# isoJTAG-Isolation.net
KiCad netlist of a schematic drawn in Altium Designer
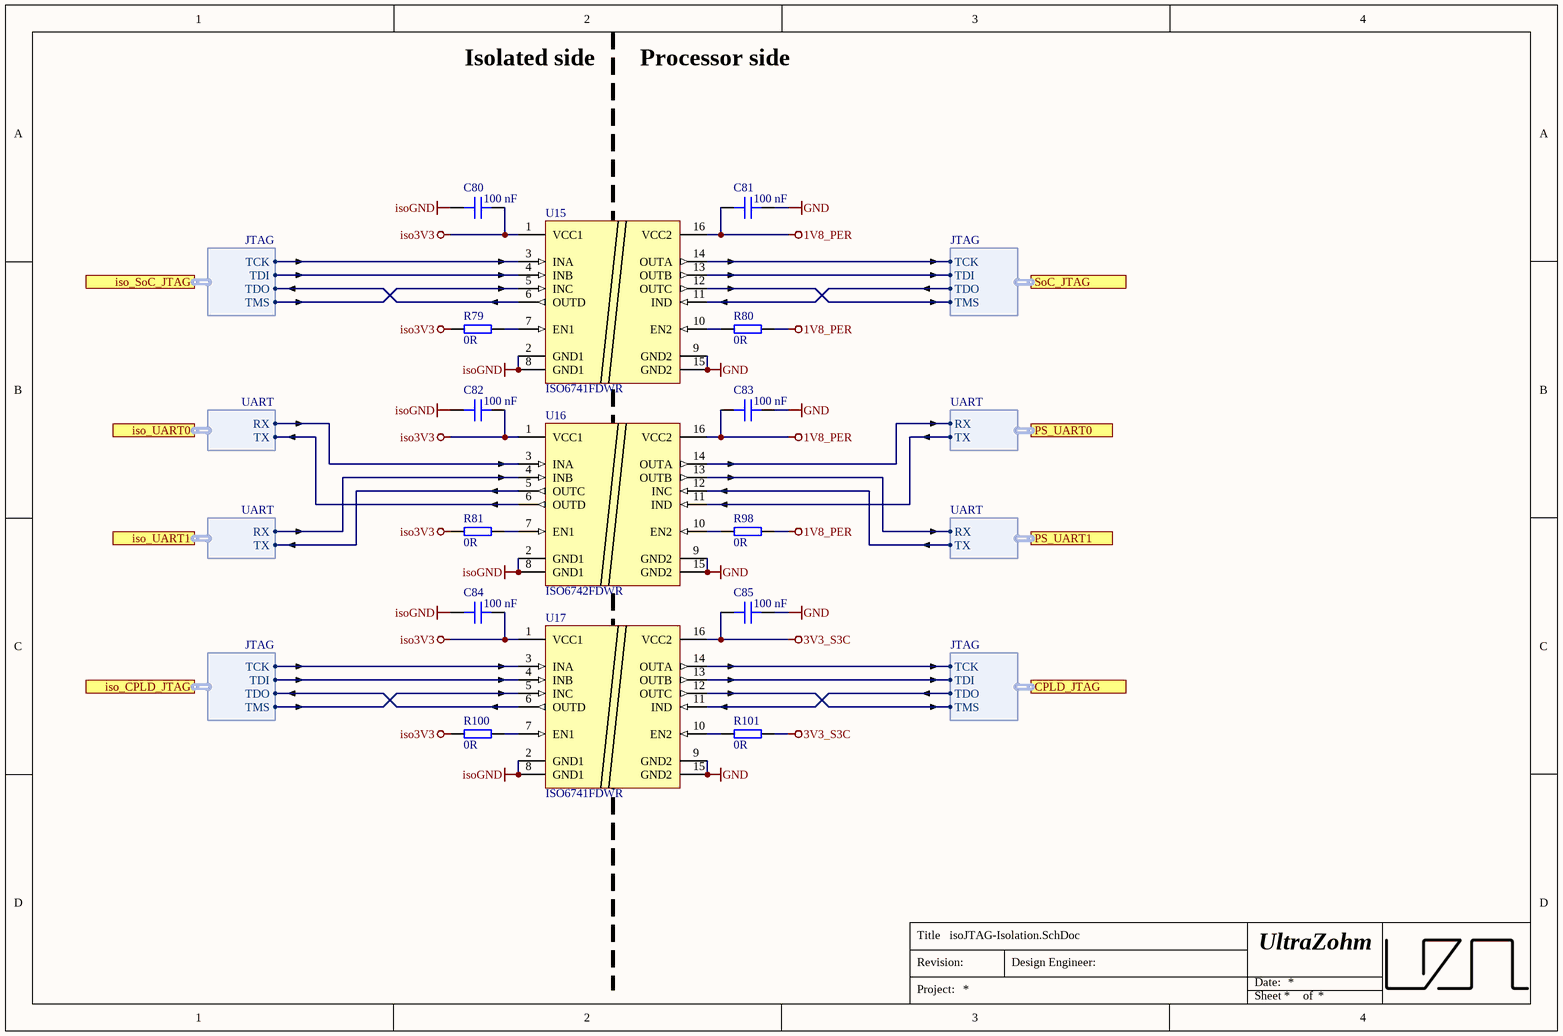
[diagram p0: isoJTAG-Isolation.SchDoc]

(export (version "E")
  (design (tool "Eeschema 10.0.6"))
  (components
    (comp (ref "C80")
      (value "100 nF")
      (footprint "C_0402_TE")
      (description "50V 100nF X7R ±10% 0402 Multilayer Ceramic Capacitors MLCC - SMD/SMT ROHS")
      (fields
        (field (name "MANUFACTURER PART NUMBER") "GRM155R71H104KE14D")
        (field (name "MANUFACTURER") "Murata Electronics")
        (field (name "CREATED FROM") "AGeiger")
      )
      (libsource (lib "user") (part "Capacitor"))
    )
    (comp (ref "C81")
      (value "100 nF")
      (footprint "C_0402_TE")
      (description "50V 100nF X7R ±10% 0402 Multilayer Ceramic Capacitors MLCC - SMD/SMT ROHS")
      (fields
        (field (name "MANUFACTURER PART NUMBER") "GRM155R71H104KE14D")
        (field (name "MANUFACTURER") "Murata Electronics")
        (field (name "CREATED FROM") "AGeiger")
      )
      (libsource (lib "user") (part "Capacitor"))
    )
    (comp (ref "C82")
      (value "100 nF")
      (footprint "C_0402_TE")
      (description "50V 100nF X7R ±10% 0402 Multilayer Ceramic Capacitors MLCC - SMD/SMT ROHS")
      (fields
        (field (name "MANUFACTURER PART NUMBER") "GRM155R71H104KE14D")
        (field (name "MANUFACTURER") "Murata Electronics")
        (field (name "CREATED FROM") "AGeiger")
      )
      (libsource (lib "user") (part "Capacitor"))
    )
    (comp (ref "C83")
      (value "100 nF")
      (footprint "C_0402_TE")
      (description "50V 100nF X7R ±10% 0402 Multilayer Ceramic Capacitors MLCC - SMD/SMT ROHS")
      (fields
        (field (name "MANUFACTURER PART NUMBER") "GRM155R71H104KE14D")
        (field (name "MANUFACTURER") "Murata Electronics")
        (field (name "CREATED FROM") "AGeiger")
      )
      (libsource (lib "user") (part "Capacitor"))
    )
    (comp (ref "C84")
      (value "100 nF")
      (footprint "C_0402_TE")
      (description "50V 100nF X7R ±10% 0402 Multilayer Ceramic Capacitors MLCC - SMD/SMT ROHS")
      (fields
        (field (name "MANUFACTURER PART NUMBER") "GRM155R71H104KE14D")
        (field (name "MANUFACTURER") "Murata Electronics")
        (field (name "CREATED FROM") "AGeiger")
      )
      (libsource (lib "user") (part "Capacitor"))
    )
    (comp (ref "C85")
      (value "100 nF")
      (footprint "C_0402_TE")
      (description "50V 100nF X7R ±10% 0402 Multilayer Ceramic Capacitors MLCC - SMD/SMT ROHS")
      (fields
        (field (name "MANUFACTURER PART NUMBER") "GRM155R71H104KE14D")
        (field (name "MANUFACTURER") "Murata Electronics")
        (field (name "CREATED FROM") "AGeiger")
      )
      (libsource (lib "user") (part "Capacitor"))
    )
    (comp (ref "R79")
      (value "0R")
      (footprint "R_0402_TE")
      (description "62.5mW Thick Film Resistors 50V 0Ω 0402 Chip Resistor - Surface Mount ROHS")
      (fields
        (field (name "MANUFACTURER PART NUMBER") "RC0402JR-070RL")
        (field (name "MANUFACTURER") "YAGEO")
        (field (name "CREATED FROM") "AGeiger")
      )
      (libsource (lib "user") (part "Resistor"))
    )
    (comp (ref "R80")
      (value "0R")
      (footprint "R_0402_TE")
      (description "62.5mW Thick Film Resistors 50V 0Ω 0402 Chip Resistor - Surface Mount ROHS")
      (fields
        (field (name "MANUFACTURER PART NUMBER") "RC0402JR-070RL")
        (field (name "MANUFACTURER") "YAGEO")
        (field (name "CREATED FROM") "AGeiger")
      )
      (libsource (lib "user") (part "Resistor"))
    )
    (comp (ref "R81")
      (value "0R")
      (footprint "R_0402_TE")
      (description "62.5mW Thick Film Resistors 50V 0Ω 0402 Chip Resistor - Surface Mount ROHS")
      (fields
        (field (name "MANUFACTURER PART NUMBER") "RC0402JR-070RL")
        (field (name "MANUFACTURER") "YAGEO")
        (field (name "CREATED FROM") "AGeiger")
      )
      (libsource (lib "user") (part "Resistor"))
    )
    (comp (ref "R98")
      (value "0R")
      (footprint "R_0402_TE")
      (description "62.5mW Thick Film Resistors 50V 0Ω 0402 Chip Resistor - Surface Mount ROHS")
      (fields
        (field (name "MANUFACTURER PART NUMBER") "RC0402JR-070RL")
        (field (name "MANUFACTURER") "YAGEO")
        (field (name "CREATED FROM") "AGeiger")
      )
      (libsource (lib "user") (part "Resistor"))
    )
    (comp (ref "R100")
      (value "0R")
      (footprint "R_0402_TE")
      (description "62.5mW Thick Film Resistors 50V 0Ω 0402 Chip Resistor - Surface Mount ROHS")
      (fields
        (field (name "MANUFACTURER PART NUMBER") "RC0402JR-070RL")
        (field (name "MANUFACTURER") "YAGEO")
        (field (name "CREATED FROM") "AGeiger")
      )
      (libsource (lib "user") (part "Resistor"))
    )
    (comp (ref "R101")
      (value "0R")
      (footprint "R_0402_TE")
      (description "62.5mW Thick Film Resistors 50V 0Ω 0402 Chip Resistor - Surface Mount ROHS")
      (fields
        (field (name "MANUFACTURER PART NUMBER") "RC0402JR-070RL")
        (field (name "MANUFACTURER") "YAGEO")
        (field (name "CREATED FROM") "AGeiger")
      )
      (libsource (lib "user") (part "Resistor"))
    )
    (comp (ref "U15")
      (value "ISO6741FDWR")
      (footprint "SOIC127P1030X265-16N")
      (description "Digital Isolators General-purpose, quad-channel, 3/1 digital isolator 16-SOIC -40 to 125")
      (fields
        (field (name "MANUFACTURER") "Texas Instruments")
        (field (name "LCSC PART NUMBER") "C5216433")
        (field (name "CREATED FROM") "FRosner")
      )
      (libsource (lib "user") (part "ISO6741"))
    )
    (comp (ref "U16")
      (value "ISO6742FDWR")
      (footprint "SOIC127P1030X265-16N")
      (description "Digital Isolators General-purpose, quad-channel, 2/2 digital isolator")
      (fields
        (field (name "MANUFACTURER") "Texas Instruments")
        (field (name "LCSC PART NUMBER") "C5216408")
        (field (name "CREATED FROM") "FRosner")
      )
      (libsource (lib "user") (part "ISO6742"))
    )
    (comp (ref "U17")
      (value "ISO6741FDWR")
      (footprint "SOIC127P1030X265-16N")
      (description "Digital Isolators General-purpose, quad-channel, 3/1 digital isolator 16-SOIC -40 to 125")
      (fields
        (field (name "MANUFACTURER") "Texas Instruments")
        (field (name "LCSC PART NUMBER") "C5216433")
        (field (name "CREATED FROM") "FRosner")
      )
      (libsource (lib "user") (part "ISO6741"))
    )
  )
  (nets
    (net (code "5") (name "1V8_PER") (class "Default")
      (node (ref "C81") (pin "2") (pinfunction "2_2") (pintype "passive"))
      (node (ref "C83") (pin "2") (pinfunction "2_2") (pintype "passive"))
      (node (ref "R80") (pin "2") (pinfunction "2_2") (pintype "passive"))
      (node (ref "R98") (pin "2") (pinfunction "2_2") (pintype "passive"))
      (node (ref "U15") (pin "16") (pinfunction "VCC2_16") (pintype "power_in"))
      (node (ref "U16") (pin "16") (pinfunction "VCC2_16") (pintype "power_in"))
    )
    (net (code "6") (name "3V3_S3C") (class "Default")
      (node (ref "C85") (pin "2") (pinfunction "2_2") (pintype "passive"))
      (node (ref "R101") (pin "2") (pinfunction "2_2") (pintype "passive"))
      (node (ref "U17") (pin "16") (pinfunction "VCC2_16") (pintype "power_in"))
    )
    (net (code "7") (name "GND") (class "Default")
      (node (ref "C81") (pin "1") (pinfunction "1_1") (pintype "passive"))
      (node (ref "C83") (pin "1") (pinfunction "1_1") (pintype "passive"))
      (node (ref "C85") (pin "1") (pinfunction "1_1") (pintype "passive"))
      (node (ref "U15") (pin "15") (pinfunction "GND2_15") (pintype "power_in"))
      (node (ref "U15") (pin "9") (pinfunction "GND2_9") (pintype "power_in"))
      (node (ref "U16") (pin "15") (pinfunction "GND2_15") (pintype "power_in"))
      (node (ref "U16") (pin "9") (pinfunction "GND2_9") (pintype "power_in"))
      (node (ref "U17") (pin "15") (pinfunction "GND2_15") (pintype "power_in"))
      (node (ref "U17") (pin "9") (pinfunction "GND2_9") (pintype "power_in"))
    )
    (net (code "8") (name "Net-(U15-EN1)") (class "Default")
      (node (ref "R79") (pin "2") (pinfunction "2_2") (pintype "passive"))
      (node (ref "U15") (pin "7") (pinfunction "EN1_7") (pintype "input"))
    )
    (net (code "9") (name "Net-(U15-EN2)") (class "Default")
      (node (ref "R80") (pin "1") (pinfunction "1_1") (pintype "passive"))
      (node (ref "U15") (pin "10") (pinfunction "EN2_10") (pintype "input"))
    )
    (net (code "10") (name "Net-(U16-EN1)") (class "Default")
      (node (ref "R81") (pin "2") (pinfunction "2_2") (pintype "passive"))
      (node (ref "U16") (pin "7") (pinfunction "EN1_7") (pintype "input"))
    )
    (net (code "11") (name "Net-(U16-EN2)") (class "Default")
      (node (ref "R98") (pin "1") (pinfunction "1_1") (pintype "passive"))
      (node (ref "U16") (pin "10") (pinfunction "EN2_10") (pintype "input"))
    )
    (net (code "12") (name "Net-(U17-EN1)") (class "Default")
      (node (ref "R100") (pin "2") (pinfunction "2_2") (pintype "passive"))
      (node (ref "U17") (pin "7") (pinfunction "EN1_7") (pintype "input"))
    )
    (net (code "13") (name "Net-(U17-EN2)") (class "Default")
      (node (ref "R101") (pin "1") (pinfunction "1_1") (pintype "passive"))
      (node (ref "U17") (pin "10") (pinfunction "EN2_10") (pintype "input"))
    )
    (net (code "14") (name "iso3V3") (class "Default")
      (node (ref "C80") (pin "1") (pinfunction "1_1") (pintype "passive"))
      (node (ref "C82") (pin "1") (pinfunction "1_1") (pintype "passive"))
      (node (ref "C84") (pin "1") (pinfunction "1_1") (pintype "passive"))
      (node (ref "R100") (pin "1") (pinfunction "1_1") (pintype "passive"))
      (node (ref "R79") (pin "1") (pinfunction "1_1") (pintype "passive"))
      (node (ref "R81") (pin "1") (pinfunction "1_1") (pintype "passive"))
      (node (ref "U15") (pin "1") (pinfunction "VCC1_1") (pintype "power_in"))
      (node (ref "U16") (pin "1") (pinfunction "VCC1_1") (pintype "power_in"))
      (node (ref "U17") (pin "1") (pinfunction "VCC1_1") (pintype "power_in"))
    )
    (net (code "15") (name "isoGND") (class "Default")
      (node (ref "C80") (pin "2") (pinfunction "2_2") (pintype "passive"))
      (node (ref "C82") (pin "2") (pinfunction "2_2") (pintype "passive"))
      (node (ref "C84") (pin "2") (pinfunction "2_2") (pintype "passive"))
      (node (ref "U15") (pin "2") (pinfunction "GND1_2") (pintype "power_in"))
      (node (ref "U15") (pin "8") (pinfunction "GND1_8") (pintype "power_in"))
      (node (ref "U16") (pin "2") (pinfunction "GND1_2") (pintype "power_in"))
      (node (ref "U16") (pin "8") (pinfunction "GND1_8") (pintype "power_in"))
      (node (ref "U17") (pin "2") (pinfunction "GND1_2") (pintype "power_in"))
      (node (ref "U17") (pin "8") (pinfunction "GND1_8") (pintype "power_in"))
    )
    (net (code "16") (name "unconnected-(U15-INA-Pad3)") (class "Default")
      (node (ref "U15") (pin "3") (pinfunction "INA_3") (pintype "input"))
    )
    (net (code "17") (name "unconnected-(U15-INB-Pad4)") (class "Default")
      (node (ref "U15") (pin "4") (pinfunction "INB_4") (pintype "input"))
    )
    (net (code "18") (name "unconnected-(U15-INC-Pad5)") (class "Default")
      (node (ref "U15") (pin "5") (pinfunction "INC_5") (pintype "input"))
    )
    (net (code "19") (name "unconnected-(U15-IND-Pad11)") (class "Default")
      (node (ref "U15") (pin "11") (pinfunction "IND_11") (pintype "input"))
    )
    (net (code "20") (name "unconnected-(U15-OUTA-Pad14)") (class "Default")
      (node (ref "U15") (pin "14") (pinfunction "OUTA_14") (pintype "output"))
    )
    (net (code "21") (name "unconnected-(U15-OUTB-Pad13)") (class "Default")
      (node (ref "U15") (pin "13") (pinfunction "OUTB_13") (pintype "output"))
    )
    (net (code "22") (name "unconnected-(U15-OUTC-Pad12)") (class "Default")
      (node (ref "U15") (pin "12") (pinfunction "OUTC_12") (pintype "output"))
    )
    (net (code "23") (name "unconnected-(U15-OUTD-Pad6)") (class "Default")
      (node (ref "U15") (pin "6") (pinfunction "OUTD_6") (pintype "output"))
    )
    (net (code "24") (name "unconnected-(U16-INA-Pad3)") (class "Default")
      (node (ref "U16") (pin "3") (pinfunction "INA_3") (pintype "input"))
    )
    (net (code "25") (name "unconnected-(U16-INB-Pad4)") (class "Default")
      (node (ref "U16") (pin "4") (pinfunction "INB_4") (pintype "input"))
    )
    (net (code "26") (name "unconnected-(U16-INC-Pad12)") (class "Default")
      (node (ref "U16") (pin "12") (pinfunction "INC_12") (pintype "input"))
    )
    (net (code "27") (name "unconnected-(U16-IND-Pad11)") (class "Default")
      (node (ref "U16") (pin "11") (pinfunction "IND_11") (pintype "input"))
    )
    (net (code "28") (name "unconnected-(U16-OUTA-Pad14)") (class "Default")
      (node (ref "U16") (pin "14") (pinfunction "OUTA_14") (pintype "output"))
    )
    (net (code "29") (name "unconnected-(U16-OUTB-Pad13)") (class "Default")
      (node (ref "U16") (pin "13") (pinfunction "OUTB_13") (pintype "output"))
    )
    (net (code "30") (name "unconnected-(U16-OUTC-Pad5)") (class "Default")
      (node (ref "U16") (pin "5") (pinfunction "OUTC_5") (pintype "output"))
    )
    (net (code "31") (name "unconnected-(U16-OUTD-Pad6)") (class "Default")
      (node (ref "U16") (pin "6") (pinfunction "OUTD_6") (pintype "output"))
    )
    (net (code "32") (name "unconnected-(U17-INA-Pad3)") (class "Default")
      (node (ref "U17") (pin "3") (pinfunction "INA_3") (pintype "input"))
    )
    (net (code "33") (name "unconnected-(U17-INB-Pad4)") (class "Default")
      (node (ref "U17") (pin "4") (pinfunction "INB_4") (pintype "input"))
    )
    (net (code "34") (name "unconnected-(U17-INC-Pad5)") (class "Default")
      (node (ref "U17") (pin "5") (pinfunction "INC_5") (pintype "input"))
    )
    (net (code "35") (name "unconnected-(U17-IND-Pad11)") (class "Default")
      (node (ref "U17") (pin "11") (pinfunction "IND_11") (pintype "input"))
    )
    (net (code "36") (name "unconnected-(U17-OUTA-Pad14)") (class "Default")
      (node (ref "U17") (pin "14") (pinfunction "OUTA_14") (pintype "output"))
    )
    (net (code "37") (name "unconnected-(U17-OUTB-Pad13)") (class "Default")
      (node (ref "U17") (pin "13") (pinfunction "OUTB_13") (pintype "output"))
    )
    (net (code "38") (name "unconnected-(U17-OUTC-Pad12)") (class "Default")
      (node (ref "U17") (pin "12") (pinfunction "OUTC_12") (pintype "output"))
    )
    (net (code "39") (name "unconnected-(U17-OUTD-Pad6)") (class "Default")
      (node (ref "U17") (pin "6") (pinfunction "OUTD_6") (pintype "output"))
    )
  )
)
